# Full.net
KiCad netlist of a schematic drawn in EAGLE
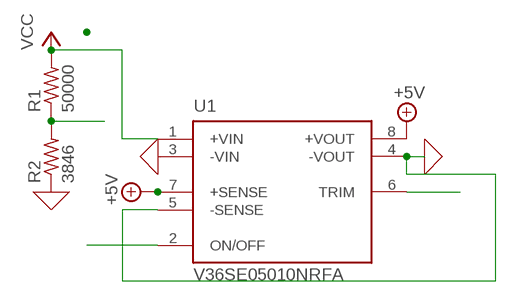
[diagram p0: schematic, sheet 1]

(export (version "E")
  (design (tool "Eeschema 10.0.6"))
  (components
    (comp (ref "R1")
      (value "50000")
      (footprint "eagle-import:0204_7")
      (libsource (lib "eagle-import") (part "R-US_0204/7"))
    )
    (comp (ref "R2")
      (value "3846")
      (footprint "eagle-import:0204_7")
      (libsource (lib "eagle-import") (part "R-US_0204/7"))
    )
    (comp (ref "U1")
      (value "V36SE05010NRFA")
      (footprint "eagle-import:MODULE_V36SE05010NRFA")
      (fields (field (name "MANUFACTURER") "Delta Electronics"))
      (libsource (lib "eagle-import") (part "V36SE05010NRFA"))
    )
  )
  (nets
    (net (code "1") (name "+5V") (class "Default")
      (node (ref "U1") (pin "7") (pinfunction "+SENSE_7") (pintype "input"))
      (node (ref "U1") (pin "8") (pinfunction "+VOUT_8") (pintype "output"))
    )
    (net (code "2") (name "GND") (class "Default")
      (node (ref "R2") (pin "1") (pinfunction "1_1") (pintype "passive"))
      (node (ref "U1") (pin "3") (pinfunction "-VIN_3") (pintype "input"))
      (node (ref "U1") (pin "4") (pinfunction "-VOUT_4") (pintype "output"))
      (node (ref "U1") (pin "5") (pinfunction "-SENSE_5") (pintype "input"))
    )
    (net (code "3") (name "Net-(R1-Pad1)") (class "Default")
      (node (ref "R1") (pin "1") (pinfunction "1_1") (pintype "passive"))
      (node (ref "R2") (pin "2") (pinfunction "2_2") (pintype "passive"))
    )
    (net (code "4") (name "VCC") (class "Default")
      (node (ref "R1") (pin "2") (pinfunction "2_2") (pintype "passive"))
      (node (ref "U1") (pin "1") (pinfunction "+VIN_1") (pintype "input"))
    )
    (net (code "5") (name "unconnected-(U1-ON{slash}OFF-Pad2)") (class "Default")
      (node (ref "U1") (pin "2") (pinfunction "ON/OFF_2") (pintype "input"))
    )
    (net (code "6") (name "unconnected-(U1-TRIM-Pad6)") (class "Default")
      (node (ref "U1") (pin "6") (pinfunction "TRIM_6") (pintype "bidirectional"))
    )
  )
)
